# Full_PCB_header_alone.net
KiCad netlist of a schematic drawn in EAGLE
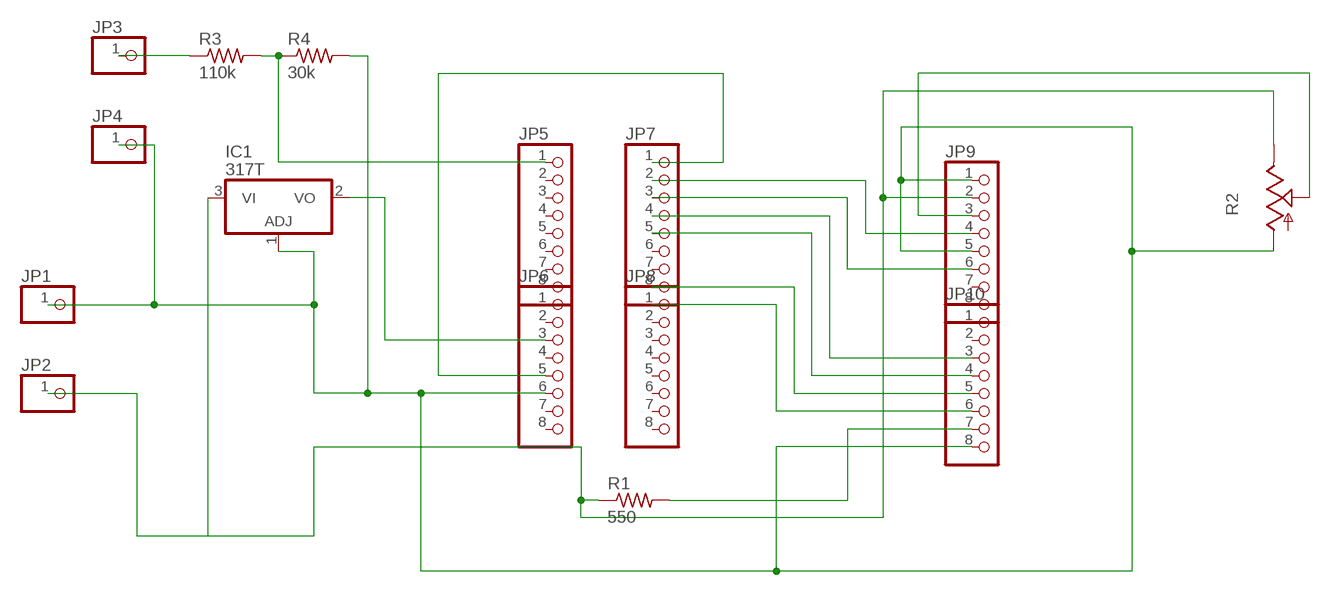
[diagram p0: schematic, sheet 1]

(export (version "E")
  (design (tool "Eeschema 10.0.6"))
  (components
    (comp (ref "IC1")
      (value "317T")
      (footprint "eagle-import:TO220H")
      (libsource (lib "eagle-import") (part "317T"))
    )
    (comp (ref "JP1")
      (value "PINHD-1X1")
      (footprint "eagle-import:1X01")
      (libsource (lib "eagle-import") (part "PINHD-1X1"))
    )
    (comp (ref "JP2")
      (value "PINHD-1X1")
      (footprint "eagle-import:1X01")
      (libsource (lib "eagle-import") (part "PINHD-1X1"))
    )
    (comp (ref "JP3")
      (value "PINHD-1X1")
      (footprint "eagle-import:1X01")
      (libsource (lib "eagle-import") (part "PINHD-1X1"))
    )
    (comp (ref "JP4")
      (value "PINHD-1X1")
      (footprint "eagle-import:1X01")
      (libsource (lib "eagle-import") (part "PINHD-1X1"))
    )
    (comp (ref "JP5")
      (value "PINHD-1X8")
      (footprint "eagle-import:1X08")
      (libsource (lib "eagle-import") (part "PINHD-1X8"))
    )
    (comp (ref "JP6")
      (value "PINHD-1X8")
      (footprint "eagle-import:1X08")
      (libsource (lib "eagle-import") (part "PINHD-1X8"))
    )
    (comp (ref "JP7")
      (value "PINHD-1X8")
      (footprint "eagle-import:1X08")
      (libsource (lib "eagle-import") (part "PINHD-1X8"))
    )
    (comp (ref "JP8")
      (value "PINHD-1X8")
      (footprint "eagle-import:1X08")
      (libsource (lib "eagle-import") (part "PINHD-1X8"))
    )
    (comp (ref "JP9")
      (value "PINHD-1X8")
      (footprint "eagle-import:1X08")
      (libsource (lib "eagle-import") (part "PINHD-1X8"))
    )
    (comp (ref "JP10")
      (value "PINHD-1X8")
      (footprint "eagle-import:1X08")
      (libsource (lib "eagle-import") (part "PINHD-1X8"))
    )
    (comp (ref "R1")
      (value "550")
      (footprint "eagle-import:0207_10")
      (libsource (lib "eagle-import") (part "R-US_0207/10"))
    )
    (comp (ref "R2")
      (value "TRIM_US-B25U")
      (footprint "eagle-import:B25U")
      (libsource (lib "eagle-import") (part "TRIM_US-B25U"))
    )
    (comp (ref "R3")
      (value "110k")
      (footprint "eagle-import:0207_10")
      (libsource (lib "eagle-import") (part "R-US_0207/10"))
    )
    (comp (ref "R4")
      (value "30k")
      (footprint "eagle-import:0207_10")
      (libsource (lib "eagle-import") (part "R-US_0207/10"))
    )
  )
  (nets
    (net (code "1") (name "Net-(IC1-ADJ)") (class "Default")
      (node (ref "IC1") (pin "1") (pinfunction "ADJ_1") (pintype "input"))
      (node (ref "JP1") (pin "1") (pinfunction "1_1") (pintype "passive"))
      (node (ref "JP10") (pin "8") (pinfunction "8_8") (pintype "passive"))
      (node (ref "JP4") (pin "1") (pinfunction "1_1") (pintype "passive"))
      (node (ref "JP6") (pin "6") (pinfunction "6_6") (pintype "passive"))
      (node (ref "JP9") (pin "1") (pinfunction "1_1") (pintype "passive"))
      (node (ref "JP9") (pin "5") (pinfunction "5_5") (pintype "passive"))
      (node (ref "R2") (pin "A") (pinfunction "A_A") (pintype "passive"))
      (node (ref "R4") (pin "2") (pinfunction "2_2") (pintype "passive"))
    )
    (net (code "2") (name "Net-(IC1-VI)") (class "Default")
      (node (ref "IC1") (pin "3") (pinfunction "VI_3") (pintype "input"))
      (node (ref "JP2") (pin "1") (pinfunction "1_1") (pintype "passive"))
      (node (ref "JP9") (pin "2") (pinfunction "2_2") (pintype "passive"))
      (node (ref "R1") (pin "1") (pinfunction "1_1") (pintype "passive"))
      (node (ref "R2") (pin "E") (pinfunction "E_E") (pintype "passive"))
    )
    (net (code "3") (name "Net-(IC1-VO)") (class "Default")
      (node (ref "IC1") (pin "2") (pinfunction "VO_2") (pintype "passive"))
      (node (ref "JP6") (pin "3") (pinfunction "3_3") (pintype "passive"))
    )
    (net (code "4") (name "Net-(JP3-Pad1)") (class "Default")
      (node (ref "JP3") (pin "1") (pinfunction "1_1") (pintype "passive"))
      (node (ref "R3") (pin "1") (pinfunction "1_1") (pintype "passive"))
    )
    (net (code "5") (name "Net-(JP5-Pad1)") (class "Default")
      (node (ref "JP5") (pin "1") (pinfunction "1_1") (pintype "passive"))
      (node (ref "R3") (pin "2") (pinfunction "2_2") (pintype "passive"))
      (node (ref "R4") (pin "1") (pinfunction "1_1") (pintype "passive"))
    )
    (net (code "6") (name "Net-(JP6-Pad5)") (class "Default")
      (node (ref "JP6") (pin "5") (pinfunction "5_5") (pintype "passive"))
      (node (ref "JP7") (pin "1") (pinfunction "1_1") (pintype "passive"))
    )
    (net (code "7") (name "Net-(JP7-Pad2)") (class "Default")
      (node (ref "JP7") (pin "2") (pinfunction "2_2") (pintype "passive"))
      (node (ref "JP9") (pin "4") (pinfunction "4_4") (pintype "passive"))
    )
    (net (code "8") (name "Net-(JP7-Pad3)") (class "Default")
      (node (ref "JP7") (pin "3") (pinfunction "3_3") (pintype "passive"))
      (node (ref "JP9") (pin "6") (pinfunction "6_6") (pintype "passive"))
    )
    (net (code "9") (name "Net-(JP9-Pad3)") (class "Default")
      (node (ref "JP9") (pin "3") (pinfunction "3_3") (pintype "passive"))
      (node (ref "R2") (pin "S") (pinfunction "S_S") (pintype "passive"))
    )
    (net (code "10") (name "Net-(JP10-Pad3)") (class "Default")
      (node (ref "JP10") (pin "3") (pinfunction "3_3") (pintype "passive"))
      (node (ref "JP7") (pin "4") (pinfunction "4_4") (pintype "passive"))
    )
    (net (code "11") (name "Net-(JP10-Pad4)") (class "Default")
      (node (ref "JP10") (pin "4") (pinfunction "4_4") (pintype "passive"))
      (node (ref "JP7") (pin "5") (pinfunction "5_5") (pintype "passive"))
    )
    (net (code "12") (name "Net-(JP10-Pad5)") (class "Default")
      (node (ref "JP10") (pin "5") (pinfunction "5_5") (pintype "passive"))
      (node (ref "JP7") (pin "8") (pinfunction "8_8") (pintype "passive"))
    )
    (net (code "13") (name "Net-(JP10-Pad6)") (class "Default")
      (node (ref "JP10") (pin "6") (pinfunction "6_6") (pintype "passive"))
      (node (ref "JP8") (pin "1") (pinfunction "1_1") (pintype "passive"))
    )
    (net (code "14") (name "Net-(JP10-Pad7)") (class "Default")
      (node (ref "JP10") (pin "7") (pinfunction "7_7") (pintype "passive"))
      (node (ref "R1") (pin "2") (pinfunction "2_2") (pintype "passive"))
    )
    (net (code "15") (name "unconnected-(JP5-Pad2)") (class "Default")
      (node (ref "JP5") (pin "2") (pinfunction "2_2") (pintype "passive"))
    )
    (net (code "16") (name "unconnected-(JP5-Pad3)") (class "Default")
      (node (ref "JP5") (pin "3") (pinfunction "3_3") (pintype "passive"))
    )
    (net (code "17") (name "unconnected-(JP5-Pad4)") (class "Default")
      (node (ref "JP5") (pin "4") (pinfunction "4_4") (pintype "passive"))
    )
    (net (code "18") (name "unconnected-(JP5-Pad5)") (class "Default")
      (node (ref "JP5") (pin "5") (pinfunction "5_5") (pintype "passive"))
    )
    (net (code "19") (name "unconnected-(JP5-Pad6)") (class "Default")
      (node (ref "JP5") (pin "6") (pinfunction "6_6") (pintype "passive"))
    )
    (net (code "20") (name "unconnected-(JP5-Pad7)") (class "Default")
      (node (ref "JP5") (pin "7") (pinfunction "7_7") (pintype "passive"))
    )
    (net (code "21") (name "unconnected-(JP5-Pad8)") (class "Default")
      (node (ref "JP5") (pin "8") (pinfunction "8_8") (pintype "passive"))
    )
    (net (code "22") (name "unconnected-(JP6-Pad1)") (class "Default")
      (node (ref "JP6") (pin "1") (pinfunction "1_1") (pintype "passive"))
    )
    (net (code "23") (name "unconnected-(JP6-Pad2)") (class "Default")
      (node (ref "JP6") (pin "2") (pinfunction "2_2") (pintype "passive"))
    )
    (net (code "24") (name "unconnected-(JP6-Pad4)") (class "Default")
      (node (ref "JP6") (pin "4") (pinfunction "4_4") (pintype "passive"))
    )
    (net (code "25") (name "unconnected-(JP6-Pad7)") (class "Default")
      (node (ref "JP6") (pin "7") (pinfunction "7_7") (pintype "passive"))
    )
    (net (code "26") (name "unconnected-(JP6-Pad8)") (class "Default")
      (node (ref "JP6") (pin "8") (pinfunction "8_8") (pintype "passive"))
    )
    (net (code "27") (name "unconnected-(JP7-Pad6)") (class "Default")
      (node (ref "JP7") (pin "6") (pinfunction "6_6") (pintype "passive"))
    )
    (net (code "28") (name "unconnected-(JP7-Pad7)") (class "Default")
      (node (ref "JP7") (pin "7") (pinfunction "7_7") (pintype "passive"))
    )
    (net (code "29") (name "unconnected-(JP8-Pad2)") (class "Default")
      (node (ref "JP8") (pin "2") (pinfunction "2_2") (pintype "passive"))
    )
    (net (code "30") (name "unconnected-(JP8-Pad3)") (class "Default")
      (node (ref "JP8") (pin "3") (pinfunction "3_3") (pintype "passive"))
    )
    (net (code "31") (name "unconnected-(JP8-Pad4)") (class "Default")
      (node (ref "JP8") (pin "4") (pinfunction "4_4") (pintype "passive"))
    )
    (net (code "32") (name "unconnected-(JP8-Pad5)") (class "Default")
      (node (ref "JP8") (pin "5") (pinfunction "5_5") (pintype "passive"))
    )
    (net (code "33") (name "unconnected-(JP8-Pad6)") (class "Default")
      (node (ref "JP8") (pin "6") (pinfunction "6_6") (pintype "passive"))
    )
    (net (code "34") (name "unconnected-(JP8-Pad7)") (class "Default")
      (node (ref "JP8") (pin "7") (pinfunction "7_7") (pintype "passive"))
    )
    (net (code "35") (name "unconnected-(JP8-Pad8)") (class "Default")
      (node (ref "JP8") (pin "8") (pinfunction "8_8") (pintype "passive"))
    )
    (net (code "36") (name "unconnected-(JP9-Pad7)") (class "Default")
      (node (ref "JP9") (pin "7") (pinfunction "7_7") (pintype "passive"))
    )
    (net (code "37") (name "unconnected-(JP9-Pad8)") (class "Default")
      (node (ref "JP9") (pin "8") (pinfunction "8_8") (pintype "passive"))
    )
    (net (code "38") (name "unconnected-(JP10-Pad1)") (class "Default")
      (node (ref "JP10") (pin "1") (pinfunction "1_1") (pintype "passive"))
    )
    (net (code "39") (name "unconnected-(JP10-Pad2)") (class "Default")
      (node (ref "JP10") (pin "2") (pinfunction "2_2") (pintype "passive"))
    )
  )
)
